# ledshield_v1_michihito.net
KiCad netlist of a schematic drawn in EAGLE
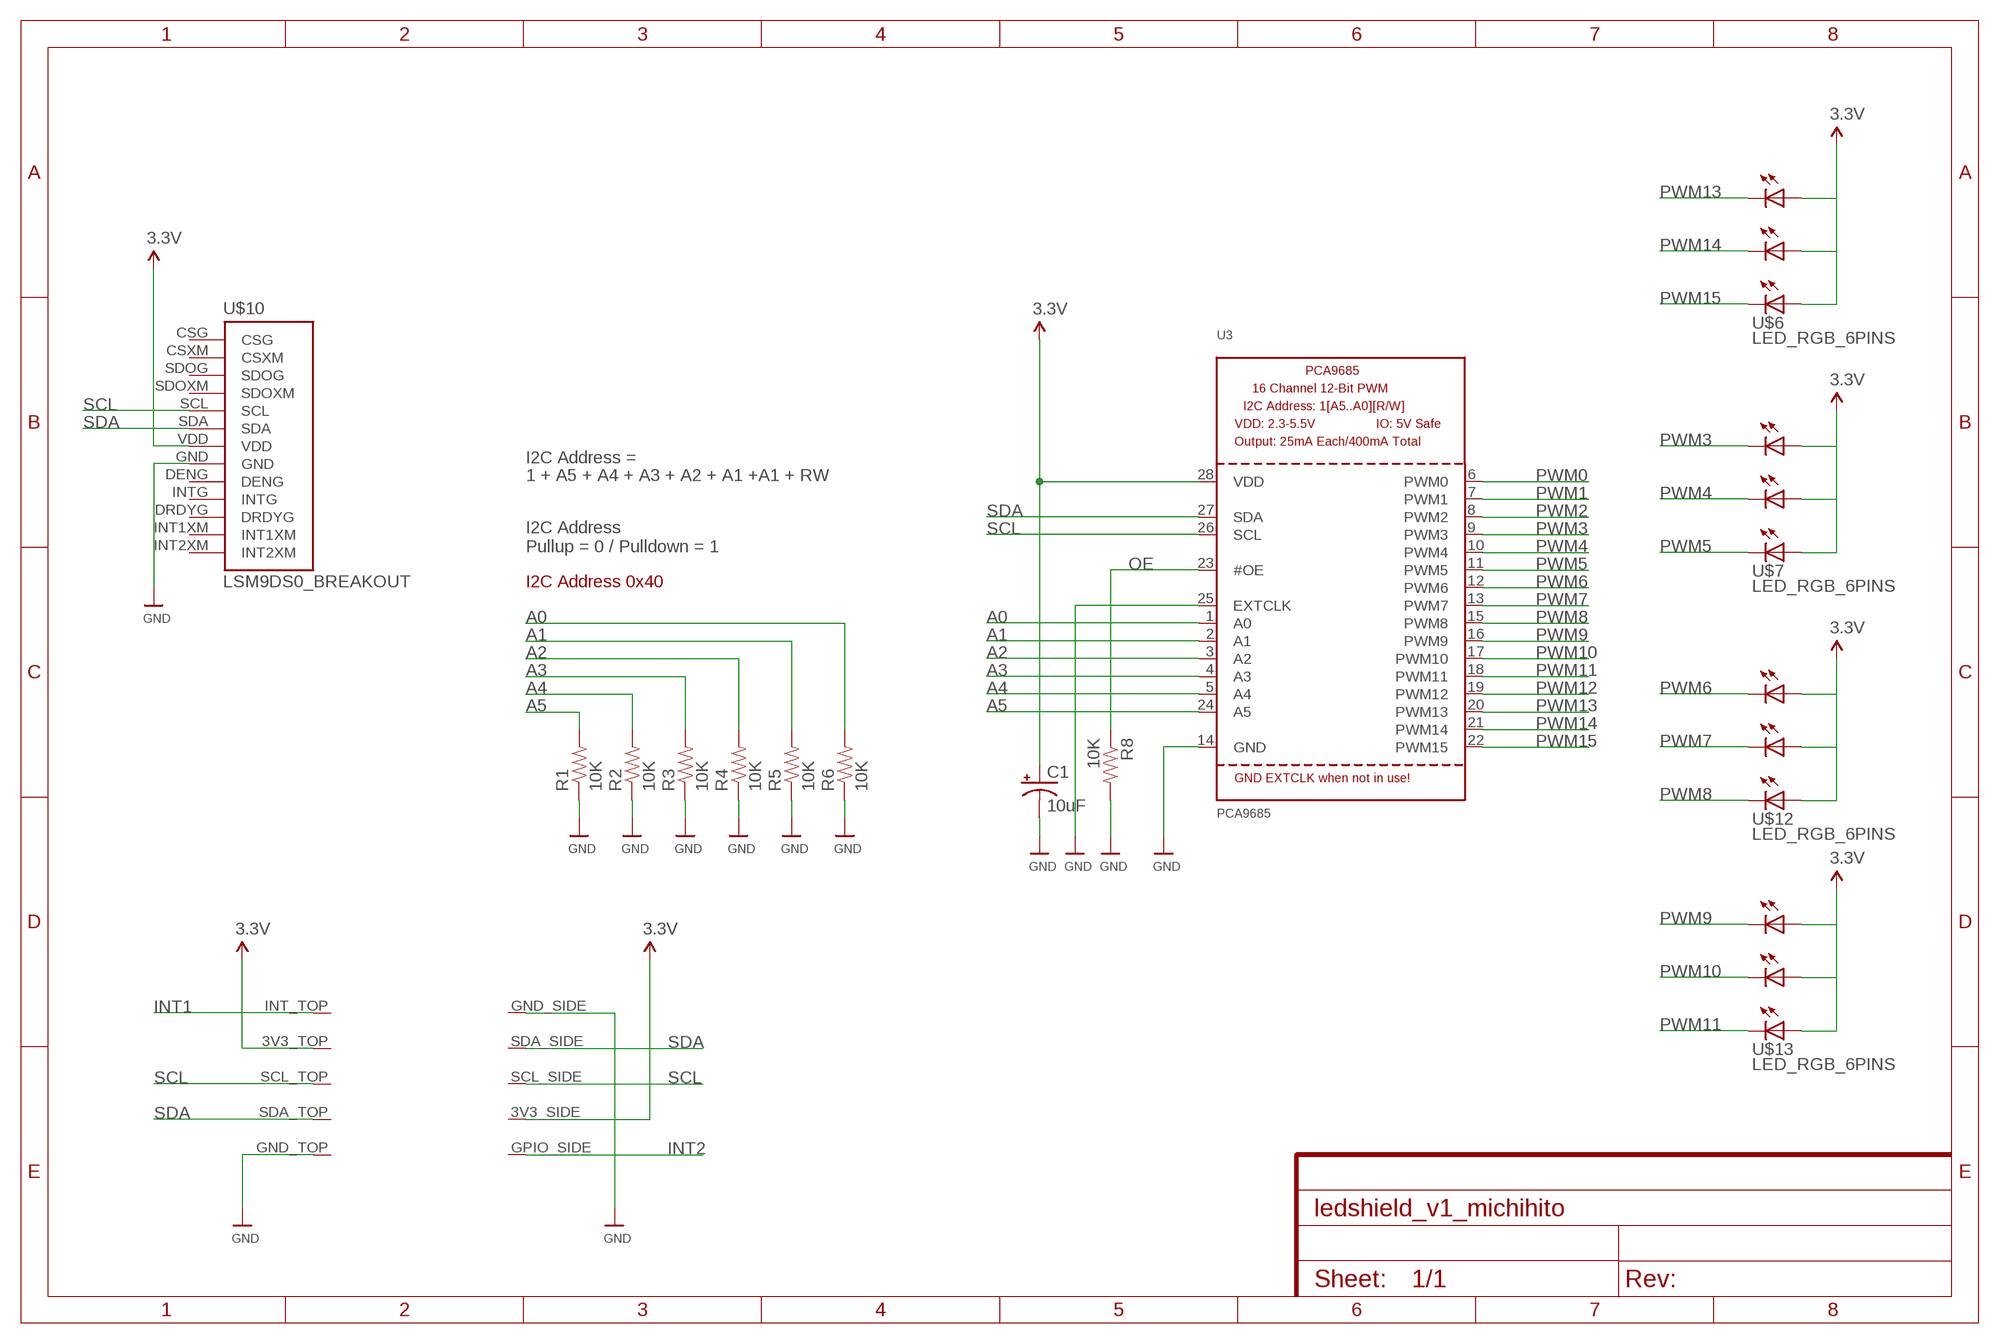
[diagram p0: schematic, sheet 1]

(export (version "E")
  (design (tool "Eeschema 10.0.6"))
  (components
    (comp (ref "C1")
      (value "10uF")
      (footprint "eagle-import:EIA3216")
      (libsource (lib "eagle-import") (part "CAP_POL1206"))
    )
    (comp (ref "R1")
      (value "10K")
      (footprint "eagle-import:1206")
      (libsource (lib "eagle-import") (part "RESISTOR1206"))
    )
    (comp (ref "R2")
      (value "10K")
      (footprint "eagle-import:1206")
      (libsource (lib "eagle-import") (part "RESISTOR1206"))
    )
    (comp (ref "R3")
      (value "10K")
      (footprint "eagle-import:1206")
      (libsource (lib "eagle-import") (part "RESISTOR1206"))
    )
    (comp (ref "R4")
      (value "10K")
      (footprint "eagle-import:1206")
      (libsource (lib "eagle-import") (part "RESISTOR1206"))
    )
    (comp (ref "R5")
      (value "10K")
      (footprint "eagle-import:1206")
      (libsource (lib "eagle-import") (part "RESISTOR1206"))
    )
    (comp (ref "R6")
      (value "10K")
      (footprint "eagle-import:1206")
      (libsource (lib "eagle-import") (part "RESISTOR1206"))
    )
    (comp (ref "R8")
      (value "10K")
      (footprint "eagle-import:1206")
      (libsource (lib "eagle-import") (part "RESISTOR1206"))
    )
    (comp (ref "U$1")
      (value "IOT_MODULE_MAIN_V2_PTH")
      (footprint "eagle-import:IOT_MODULE_MAIN_V3_PTH")
      (libsource (lib "eagle-import") (part "IOT_MODULE_MAIN_V2_PTH"))
    )
    (comp (ref "U$6")
      (value "LED_RGB_6PINS")
      (footprint "eagle-import:LED_RGB_6PINS")
      (libsource (lib "eagle-import") (part "LED_RGB_6PINS"))
    )
    (comp (ref "U$7")
      (value "LED_RGB_6PINS")
      (footprint "eagle-import:LED_RGB_6PINS")
      (libsource (lib "eagle-import") (part "LED_RGB_6PINS"))
    )
    (comp (ref "U$10")
      (value "LSM9DS0_BREAKOUT")
      (footprint "eagle-import:LSM9DS0_BREAKOUT")
      (libsource (lib "eagle-import") (part "LSM9DS0_BREAKOUT"))
    )
    (comp (ref "U$12")
      (value "LED_RGB_6PINS")
      (footprint "eagle-import:LED_RGB_6PINS")
      (libsource (lib "eagle-import") (part "LED_RGB_6PINS"))
    )
    (comp (ref "U$13")
      (value "LED_RGB_6PINS")
      (footprint "eagle-import:LED_RGB_6PINS")
      (libsource (lib "eagle-import") (part "LED_RGB_6PINS"))
    )
    (comp (ref "U3")
      (value "PCA9685")
      (footprint "eagle-import:TSSOP28")
      (libsource (lib "eagle-import") (part "PCA9685"))
    )
  )
  (nets
    (net (code "1") (name "/A0") (class "Default")
      (node (ref "R6") (pin "2") (pinfunction "2_2") (pintype "passive"))
      (node (ref "U3") (pin "1") (pinfunction "A0_1") (pintype "bidirectional"))
    )
    (net (code "2") (name "/A1") (class "Default")
      (node (ref "R5") (pin "2") (pinfunction "2_2") (pintype "passive"))
      (node (ref "U3") (pin "2") (pinfunction "A1_2") (pintype "bidirectional"))
    )
    (net (code "3") (name "/A2") (class "Default")
      (node (ref "R4") (pin "2") (pinfunction "2_2") (pintype "passive"))
      (node (ref "U3") (pin "3") (pinfunction "A2_3") (pintype "bidirectional"))
    )
    (net (code "4") (name "/A3") (class "Default")
      (node (ref "R3") (pin "2") (pinfunction "2_2") (pintype "passive"))
      (node (ref "U3") (pin "4") (pinfunction "A3_4") (pintype "bidirectional"))
    )
    (net (code "5") (name "/A4") (class "Default")
      (node (ref "R2") (pin "2") (pinfunction "2_2") (pintype "passive"))
      (node (ref "U3") (pin "5") (pinfunction "A4_5") (pintype "bidirectional"))
    )
    (net (code "6") (name "/A5") (class "Default")
      (node (ref "R1") (pin "2") (pinfunction "2_2") (pintype "passive"))
      (node (ref "U3") (pin "24") (pinfunction "A5_24") (pintype "bidirectional"))
    )
    (net (code "7") (name "/INT1") (class "Default")
      (node (ref "U$1") (pin "INT_TOP") (pinfunction "INT_TOP_INT_TOP") (pintype "bidirectional"))
    )
    (net (code "8") (name "/INT2") (class "Default")
      (node (ref "U$1") (pin "GPIO_SIDE") (pinfunction "GPIO_SIDE_GPIO_SIDE") (pintype "bidirectional"))
    )
    (net (code "9") (name "/OE") (class "Default")
      (node (ref "R8") (pin "1") (pinfunction "1_1") (pintype "passive"))
      (node (ref "U3") (pin "23") (pinfunction "#OE_23") (pintype "input"))
    )
    (net (code "10") (name "/PWM0") (class "Default")
      (node (ref "U3") (pin "6") (pinfunction "PWM0_6") (pintype "output"))
    )
    (net (code "11") (name "/PWM1") (class "Default")
      (node (ref "U3") (pin "7") (pinfunction "PWM1_7") (pintype "output"))
    )
    (net (code "12") (name "/PWM2") (class "Default")
      (node (ref "U3") (pin "8") (pinfunction "PWM2_8") (pintype "output"))
    )
    (net (code "13") (name "/PWM3") (class "Default")
      (node (ref "U$7") (pin "BC") (pinfunction "BC_BC") (pintype "passive"))
      (node (ref "U3") (pin "9") (pinfunction "PWM3_9") (pintype "output"))
    )
    (net (code "14") (name "/PWM4") (class "Default")
      (node (ref "U$7") (pin "RC") (pinfunction "RC_RC") (pintype "passive"))
      (node (ref "U3") (pin "10") (pinfunction "PWM4_10") (pintype "output"))
    )
    (net (code "15") (name "/PWM5") (class "Default")
      (node (ref "U$7") (pin "GC") (pinfunction "GC_GC") (pintype "passive"))
      (node (ref "U3") (pin "11") (pinfunction "PWM5_11") (pintype "output"))
    )
    (net (code "16") (name "/PWM6") (class "Default")
      (node (ref "U$12") (pin "BC") (pinfunction "BC_BC") (pintype "passive"))
      (node (ref "U3") (pin "12") (pinfunction "PWM6_12") (pintype "output"))
    )
    (net (code "17") (name "/PWM7") (class "Default")
      (node (ref "U$12") (pin "RC") (pinfunction "RC_RC") (pintype "passive"))
      (node (ref "U3") (pin "13") (pinfunction "PWM7_13") (pintype "output"))
    )
    (net (code "18") (name "/PWM8") (class "Default")
      (node (ref "U$12") (pin "GC") (pinfunction "GC_GC") (pintype "passive"))
      (node (ref "U3") (pin "15") (pinfunction "PWM8_15") (pintype "output"))
    )
    (net (code "19") (name "/PWM9") (class "Default")
      (node (ref "U$13") (pin "BC") (pinfunction "BC_BC") (pintype "passive"))
      (node (ref "U3") (pin "16") (pinfunction "PWM9_16") (pintype "output"))
    )
    (net (code "20") (name "/PWM10") (class "Default")
      (node (ref "U$13") (pin "RC") (pinfunction "RC_RC") (pintype "passive"))
      (node (ref "U3") (pin "17") (pinfunction "PWM10_17") (pintype "output"))
    )
    (net (code "21") (name "/PWM11") (class "Default")
      (node (ref "U$13") (pin "GC") (pinfunction "GC_GC") (pintype "passive"))
      (node (ref "U3") (pin "18") (pinfunction "PWM11_18") (pintype "output"))
    )
    (net (code "22") (name "/PWM12") (class "Default")
      (node (ref "U3") (pin "19") (pinfunction "PWM12_19") (pintype "output"))
    )
    (net (code "23") (name "/PWM13") (class "Default")
      (node (ref "U$6") (pin "BC") (pinfunction "BC_BC") (pintype "passive"))
      (node (ref "U3") (pin "20") (pinfunction "PWM13_20") (pintype "output"))
    )
    (net (code "24") (name "/PWM14") (class "Default")
      (node (ref "U$6") (pin "RC") (pinfunction "RC_RC") (pintype "passive"))
      (node (ref "U3") (pin "21") (pinfunction "PWM14_21") (pintype "output"))
    )
    (net (code "25") (name "/PWM15") (class "Default")
      (node (ref "U$6") (pin "GC") (pinfunction "GC_GC") (pintype "passive"))
      (node (ref "U3") (pin "22") (pinfunction "PWM15_22") (pintype "output"))
    )
    (net (code "26") (name "/SCL") (class "Default")
      (node (ref "U$1") (pin "SCL_SIDE") (pinfunction "SCL_SIDE_SCL_SIDE") (pintype "bidirectional"))
      (node (ref "U$1") (pin "SCL_TOP") (pinfunction "SCL_TOP_SCL_TOP") (pintype "bidirectional"))
      (node (ref "U$10") (pin "SCL") (pinfunction "SCL_SCL") (pintype "bidirectional"))
      (node (ref "U3") (pin "26") (pinfunction "SCL_26") (pintype "bidirectional"))
    )
    (net (code "27") (name "/SDA") (class "Default")
      (node (ref "U$1") (pin "SDA_SIDE") (pinfunction "SDA_SIDE_SDA_SIDE") (pintype "bidirectional"))
      (node (ref "U$1") (pin "SDA_TOP") (pinfunction "SDA_TOP_SDA_TOP") (pintype "bidirectional"))
      (node (ref "U$10") (pin "SDA") (pinfunction "SDA_SDA") (pintype "bidirectional"))
      (node (ref "U3") (pin "27") (pinfunction "SDA_27") (pintype "bidirectional"))
    )
    (net (code "28") (name "3.3V") (class "Default")
      (node (ref "C1") (pin "A") (pinfunction "+_A") (pintype "passive"))
      (node (ref "U$1") (pin "3V3_SIDE") (pinfunction "3V3_SIDE_3V3_SIDE") (pintype "bidirectional"))
      (node (ref "U$1") (pin "3V3_TOP") (pinfunction "3V3_TOP_3V3_TOP") (pintype "bidirectional"))
      (node (ref "U$10") (pin "VDD") (pinfunction "VDD_VDD") (pintype "power_in"))
      (node (ref "U$12") (pin "BA") (pinfunction "BA_BA") (pintype "passive"))
      (node (ref "U$12") (pin "GA") (pinfunction "GA_GA") (pintype "passive"))
      (node (ref "U$12") (pin "RA") (pinfunction "RA_RA") (pintype "passive"))
      (node (ref "U$13") (pin "BA") (pinfunction "BA_BA") (pintype "passive"))
      (node (ref "U$13") (pin "GA") (pinfunction "GA_GA") (pintype "passive"))
      (node (ref "U$13") (pin "RA") (pinfunction "RA_RA") (pintype "passive"))
      (node (ref "U$6") (pin "BA") (pinfunction "BA_BA") (pintype "passive"))
      (node (ref "U$6") (pin "GA") (pinfunction "GA_GA") (pintype "passive"))
      (node (ref "U$6") (pin "RA") (pinfunction "RA_RA") (pintype "passive"))
      (node (ref "U$7") (pin "BA") (pinfunction "BA_BA") (pintype "passive"))
      (node (ref "U$7") (pin "GA") (pinfunction "GA_GA") (pintype "passive"))
      (node (ref "U$7") (pin "RA") (pinfunction "RA_RA") (pintype "passive"))
      (node (ref "U3") (pin "28") (pinfunction "VDD_28") (pintype "power_in"))
    )
    (net (code "29") (name "GND") (class "Default")
      (node (ref "C1") (pin "C") (pinfunction "-_C") (pintype "passive"))
      (node (ref "R1") (pin "1") (pinfunction "1_1") (pintype "passive"))
      (node (ref "R2") (pin "1") (pinfunction "1_1") (pintype "passive"))
      (node (ref "R3") (pin "1") (pinfunction "1_1") (pintype "passive"))
      (node (ref "R4") (pin "1") (pinfunction "1_1") (pintype "passive"))
      (node (ref "R5") (pin "1") (pinfunction "1_1") (pintype "passive"))
      (node (ref "R6") (pin "1") (pinfunction "1_1") (pintype "passive"))
      (node (ref "R8") (pin "2") (pinfunction "2_2") (pintype "passive"))
      (node (ref "U$1") (pin "GND_SIDE") (pinfunction "GND_SIDE_GND_SIDE") (pintype "bidirectional"))
      (node (ref "U$1") (pin "GND_TOP") (pinfunction "GND_TOP_GND_TOP") (pintype "bidirectional"))
      (node (ref "U$10") (pin "GND") (pinfunction "GND_GND") (pintype "power_in"))
      (node (ref "U3") (pin "14") (pinfunction "GND_14") (pintype "power_in"))
      (node (ref "U3") (pin "25") (pinfunction "EXTCLK_25") (pintype "input"))
    )
    (net (code "30") (name "unconnected-(U$10-PadCSG)") (class "Default")
      (node (ref "U$10") (pin "CSG") (pinfunction "CSG_CSG") (pintype "bidirectional"))
    )
    (net (code "31") (name "unconnected-(U$10-PadCSXM)") (class "Default")
      (node (ref "U$10") (pin "CSXM") (pinfunction "CSXM_CSXM") (pintype "bidirectional"))
    )
    (net (code "32") (name "unconnected-(U$10-PadDENG)") (class "Default")
      (node (ref "U$10") (pin "DENG") (pinfunction "DENG_DENG") (pintype "bidirectional"))
    )
    (net (code "33") (name "unconnected-(U$10-PadDRDYG)") (class "Default")
      (node (ref "U$10") (pin "DRDYG") (pinfunction "DRDYG_DRDYG") (pintype "bidirectional"))
    )
    (net (code "34") (name "unconnected-(U$10-PadINT1XM)") (class "Default")
      (node (ref "U$10") (pin "INT1XM") (pinfunction "INT1XM_INT1XM") (pintype "bidirectional"))
    )
    (net (code "35") (name "unconnected-(U$10-PadINT2XM)") (class "Default")
      (node (ref "U$10") (pin "INT2XM") (pinfunction "INT2XM_INT2XM") (pintype "bidirectional"))
    )
    (net (code "36") (name "unconnected-(U$10-PadINTG)") (class "Default")
      (node (ref "U$10") (pin "INTG") (pinfunction "INTG_INTG") (pintype "bidirectional"))
    )
    (net (code "37") (name "unconnected-(U$10-PadSDOG)") (class "Default")
      (node (ref "U$10") (pin "SDOG") (pinfunction "SDOG_SDOG") (pintype "bidirectional"))
    )
    (net (code "38") (name "unconnected-(U$10-PadSDOXM)") (class "Default")
      (node (ref "U$10") (pin "SDOXM") (pinfunction "SDOXM_SDOXM") (pintype "bidirectional"))
    )
  )
)
